# ProPrj_Gardening_IoT_2026-04-28.net
KiCad netlist of a schematic drawn in EasyEDA Pro
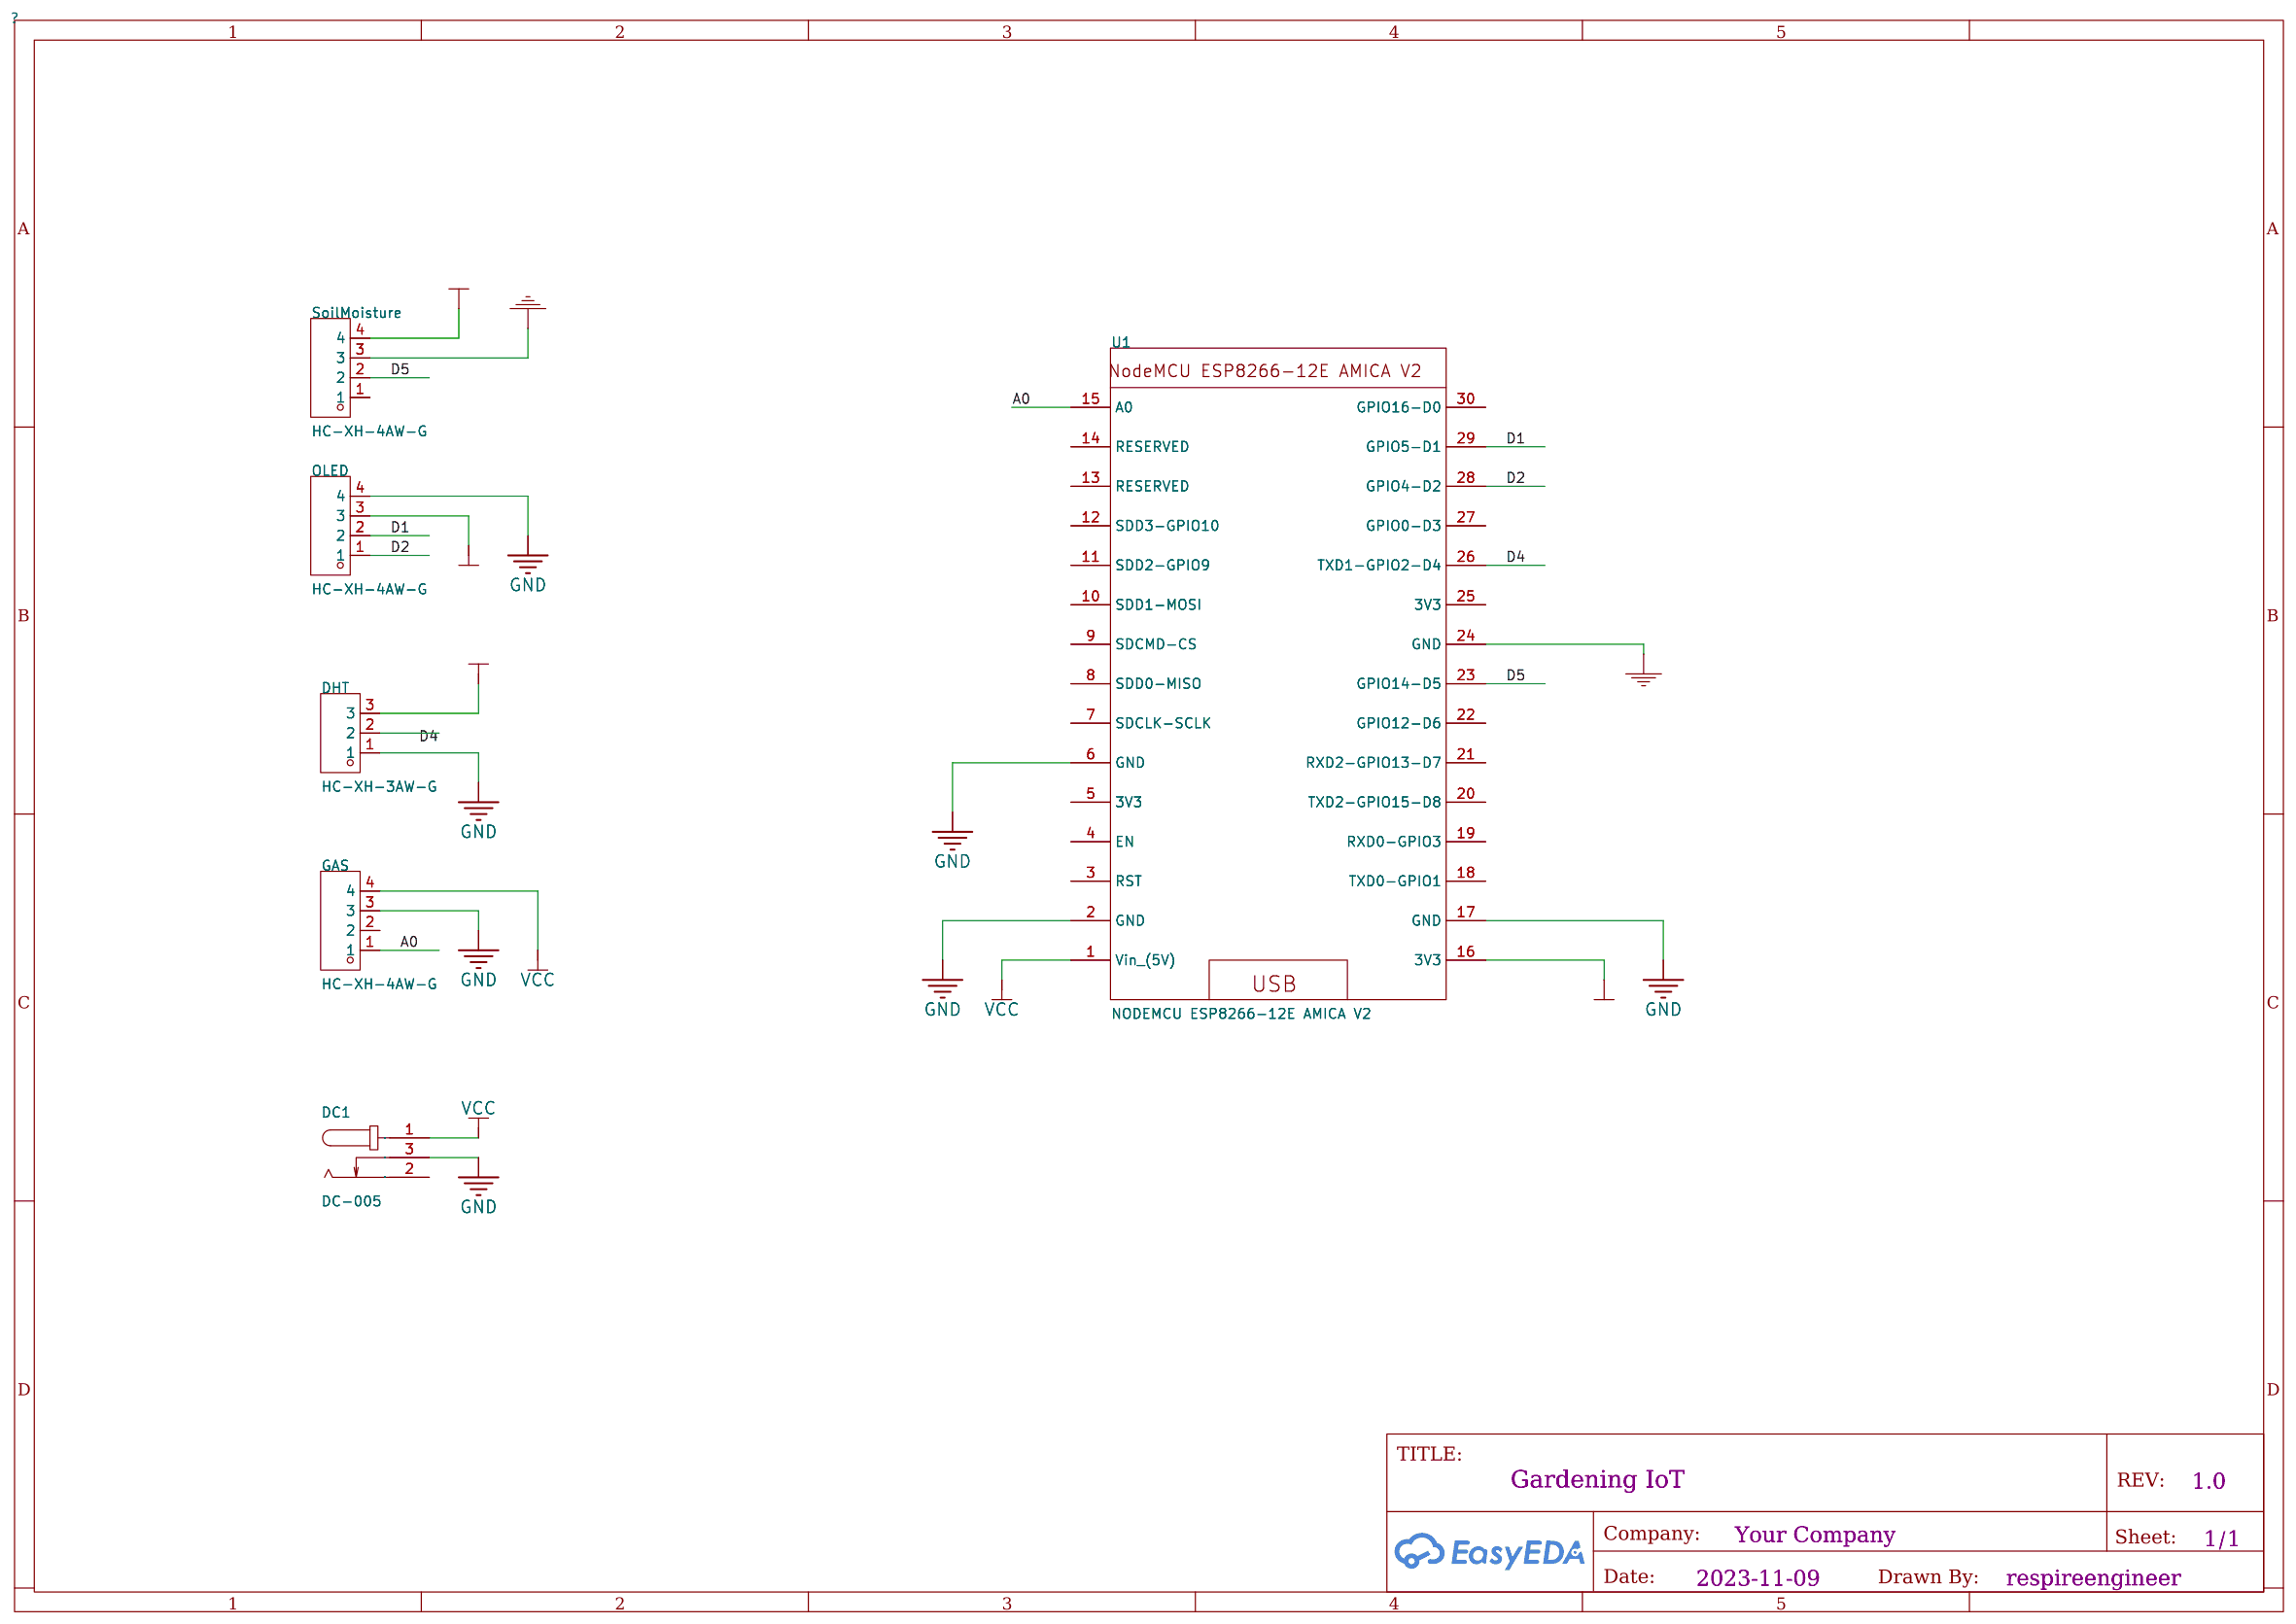
[diagram p0: schematic sheet]

(export (version "E")
  (design (tool "Eeschema 10.0.6"))
  (components
    (comp (ref "DC1")
      (value "DC-005")
      (footprint "easyedapro:DC-IN-TH_DC-005-A")
      (libsource (lib "easyedapro") (part "DC-005"))
    )
    (comp (ref "DHT")
      (value "HC-XH-3AW-G")
      (footprint "easyedapro:CONN-TH_3P-P2.50_HC-XH-3AW-G")
      (fields (field (name "Manufacturer") "HCTL(华灿天禄)"))
      (libsource (lib "easyedapro") (part "HC-XH-3AW-G"))
    )
    (comp (ref "GAS")
      (value "HC-XH-4AW-G")
      (footprint "easyedapro:CONN-TH_4P-P2.50_HC-XH-4AW-G")
      (fields (field (name "Manufacturer") "HCTL(华灿天禄)"))
      (libsource (lib "easyedapro") (part "HC-XH-4AW-G"))
    )
    (comp (ref "OLED")
      (value "HC-XH-4AW-G")
      (footprint "easyedapro:CONN-TH_4P-P2.50_HC-XH-4AW-G")
      (fields (field (name "Manufacturer") "HCTL(华灿天禄)"))
      (libsource (lib "easyedapro") (part "HC-XH-4AW-G"))
    )
    (comp (ref "SoilMoisture")
      (value "HC-XH-4AW-G")
      (footprint "easyedapro:CONN-TH_4P-P2.50_HC-XH-4AW-G")
      (fields (field (name "Manufacturer") "HCTL(华灿天禄)"))
      (libsource (lib "easyedapro") (part "HC-XH-4AW-G"))
    )
    (comp (ref "U1")
      (value "NODEMCU ESP8266-12E AMICA V2")
      (footprint "easyedapro:NODEMCU ESP8266-12E AMICA V2")
      (description "NodeMCU Lua Amica Module V2 ESP8266 ESP-12F WIFI Wifi Development Board avec CP2102")
      (fields (field (name "Manufacturer") "AZ-Delivery"))
      (libsource (lib "easyedapro") (part "NODEMCU ESP8266-12E AMICA V2"))
    )
  )
  (nets
    (net (code "1") (name "/A0") (class "Default")
      (node (ref "GAS") (pin "1") (pinfunction "1_1") (pintype "unspecified"))
      (node (ref "U1") (pin "15") (pinfunction "A0_15") (pintype "bidirectional"))
    )
    (net (code "2") (name "/D1") (class "Default")
      (node (ref "OLED") (pin "2") (pinfunction "2_2") (pintype "unspecified"))
      (node (ref "U1") (pin "29") (pinfunction "GPIO5-D1_29") (pintype "unspecified"))
    )
    (net (code "3") (name "/D2") (class "Default")
      (node (ref "OLED") (pin "1") (pinfunction "1_1") (pintype "unspecified"))
      (node (ref "U1") (pin "28") (pinfunction "GPIO4-D2_28") (pintype "unspecified"))
    )
    (net (code "4") (name "/D4") (class "Default")
      (node (ref "DHT") (pin "2") (pinfunction "2_2") (pintype "unspecified"))
      (node (ref "U1") (pin "26") (pinfunction "TXD1-GPIO2-D4_26") (pintype "unspecified"))
    )
    (net (code "5") (name "/D5") (class "Default")
      (node (ref "SoilMoisture") (pin "2") (pinfunction "2_2") (pintype "unspecified"))
      (node (ref "U1") (pin "23") (pinfunction "GPIO14-D5_23") (pintype "unspecified"))
    )
    (net (code "6") (name "GND") (class "Default")
      (node (ref "DC1") (pin "3") (pinfunction "3_3") (pintype "unspecified"))
      (node (ref "DHT") (pin "1") (pinfunction "1_1") (pintype "unspecified"))
      (node (ref "GAS") (pin "3") (pinfunction "3_3") (pintype "unspecified"))
      (node (ref "OLED") (pin "4") (pinfunction "4_4") (pintype "unspecified"))
      (node (ref "SoilMoisture") (pin "3") (pinfunction "3_3") (pintype "unspecified"))
      (node (ref "U1") (pin "17") (pinfunction "GND_17") (pintype "unspecified"))
      (node (ref "U1") (pin "2") (pinfunction "GND_2") (pintype "unspecified"))
      (node (ref "U1") (pin "24") (pinfunction "GND_24") (pintype "unspecified"))
      (node (ref "U1") (pin "6") (pinfunction "GND_6") (pintype "unspecified"))
    )
    (net (code "7") (name "VCC") (class "Default")
      (node (ref "DC1") (pin "1") (pinfunction "1_1") (pintype "unspecified"))
      (node (ref "GAS") (pin "4") (pinfunction "4_4") (pintype "unspecified"))
      (node (ref "U1") (pin "1") (pinfunction "Vin_(5V)_1") (pintype "unspecified"))
    )
    (net (code "8") (name "VCC2") (class "Default")
      (node (ref "DHT") (pin "3") (pinfunction "3_3") (pintype "unspecified"))
      (node (ref "OLED") (pin "3") (pinfunction "3_3") (pintype "unspecified"))
      (node (ref "SoilMoisture") (pin "4") (pinfunction "4_4") (pintype "unspecified"))
      (node (ref "U1") (pin "16") (pinfunction "3V3_16") (pintype "unspecified"))
    )
    (net (code "9") (name "unconnected-(DC1-Pad2)") (class "Default")
      (node (ref "DC1") (pin "2") (pinfunction "2_2") (pintype "unspecified"))
    )
    (net (code "10") (name "unconnected-(GAS-Pad2)") (class "Default")
      (node (ref "GAS") (pin "2") (pinfunction "2_2") (pintype "unspecified"))
    )
    (net (code "11") (name "unconnected-(SoilMoisture-Pad1)") (class "Default")
      (node (ref "SoilMoisture") (pin "1") (pinfunction "1_1") (pintype "unspecified"))
    )
    (net (code "12") (name "unconnected-(U1-3V3-Pad5)") (class "Default")
      (node (ref "U1") (pin "5") (pinfunction "3V3_5") (pintype "unspecified"))
    )
    (net (code "13") (name "unconnected-(U1-3V3-Pad25)") (class "Default")
      (node (ref "U1") (pin "25") (pinfunction "3V3_25") (pintype "unspecified"))
    )
    (net (code "14") (name "unconnected-(U1-EN-Pad4)") (class "Default")
      (node (ref "U1") (pin "4") (pinfunction "EN_4") (pintype "unspecified"))
    )
    (net (code "15") (name "unconnected-(U1-GPIO0-D3-Pad27)") (class "Default")
      (node (ref "U1") (pin "27") (pinfunction "GPIO0-D3_27") (pintype "unspecified"))
    )
    (net (code "16") (name "unconnected-(U1-GPIO12-D6-Pad22)") (class "Default")
      (node (ref "U1") (pin "22") (pinfunction "GPIO12-D6_22") (pintype "unspecified"))
    )
    (net (code "17") (name "unconnected-(U1-GPIO16-D0-Pad30)") (class "Default")
      (node (ref "U1") (pin "30") (pinfunction "GPIO16-D0_30") (pintype "unspecified"))
    )
    (net (code "18") (name "unconnected-(U1-RESERVED-Pad13)") (class "Default")
      (node (ref "U1") (pin "13") (pinfunction "RESERVED_13") (pintype "unspecified"))
    )
    (net (code "19") (name "unconnected-(U1-RESERVED-Pad14)") (class "Default")
      (node (ref "U1") (pin "14") (pinfunction "RESERVED_14") (pintype "unspecified"))
    )
    (net (code "20") (name "unconnected-(U1-RST-Pad3)") (class "Default")
      (node (ref "U1") (pin "3") (pinfunction "RST_3") (pintype "unspecified"))
    )
    (net (code "21") (name "unconnected-(U1-RXD0-GPIO3-Pad19)") (class "Default")
      (node (ref "U1") (pin "19") (pinfunction "RXD0-GPIO3_19") (pintype "unspecified"))
    )
    (net (code "22") (name "unconnected-(U1-RXD2-GPIO13-D7-Pad21)") (class "Default")
      (node (ref "U1") (pin "21") (pinfunction "RXD2-GPIO13-D7_21") (pintype "unspecified"))
    )
    (net (code "23") (name "unconnected-(U1-SDCLK-SCLK-Pad7)") (class "Default")
      (node (ref "U1") (pin "7") (pinfunction "SDCLK-SCLK_7") (pintype "unspecified"))
    )
    (net (code "24") (name "unconnected-(U1-SDCMD-CS-Pad9)") (class "Default")
      (node (ref "U1") (pin "9") (pinfunction "SDCMD-CS_9") (pintype "unspecified"))
    )
    (net (code "25") (name "unconnected-(U1-SDD0-MISO-Pad8)") (class "Default")
      (node (ref "U1") (pin "8") (pinfunction "SDD0-MISO_8") (pintype "unspecified"))
    )
    (net (code "26") (name "unconnected-(U1-SDD1-MOSI-Pad10)") (class "Default")
      (node (ref "U1") (pin "10") (pinfunction "SDD1-MOSI_10") (pintype "unspecified"))
    )
    (net (code "27") (name "unconnected-(U1-SDD2-GPIO9-Pad11)") (class "Default")
      (node (ref "U1") (pin "11") (pinfunction "SDD2-GPIO9_11") (pintype "unspecified"))
    )
    (net (code "28") (name "unconnected-(U1-SDD3-GPIO10-Pad12)") (class "Default")
      (node (ref "U1") (pin "12") (pinfunction "SDD3-GPIO10_12") (pintype "unspecified"))
    )
    (net (code "29") (name "unconnected-(U1-TXD0-GPIO1-Pad18)") (class "Default")
      (node (ref "U1") (pin "18") (pinfunction "TXD0-GPIO1_18") (pintype "unspecified"))
    )
    (net (code "30") (name "unconnected-(U1-TXD2-GPIO15-D8-Pad20)") (class "Default")
      (node (ref "U1") (pin "20") (pinfunction "TXD2-GPIO15-D8_20") (pintype "unspecified"))
    )
  )
)
